# emonVS_mini.net
KiCad netlist of a schematic drawn in EAGLE
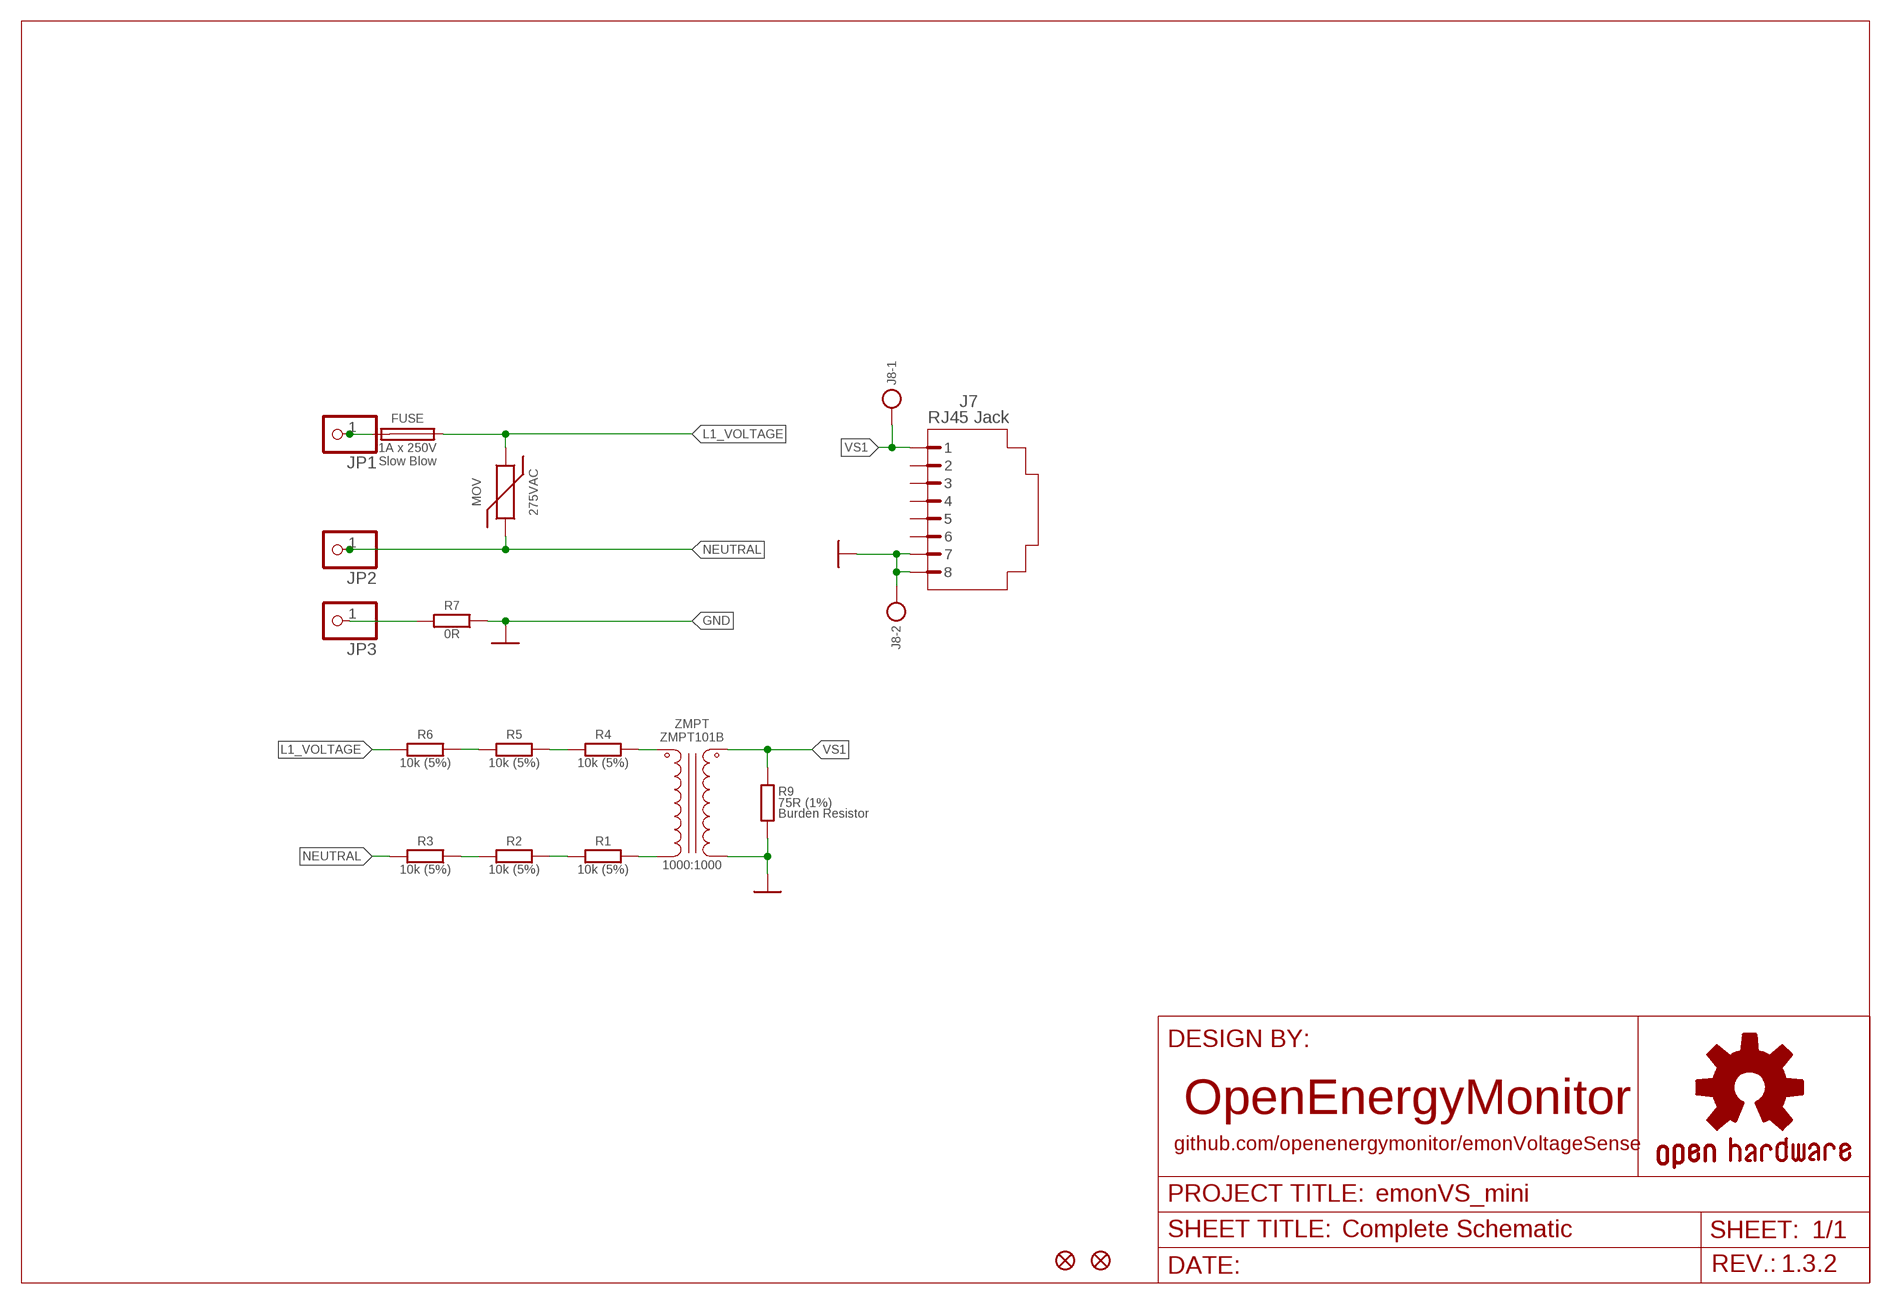
[diagram p0: schematic, sheet 1]

(export (version "E")
  (design (tool "Eeschema 10.0.6"))
  (components
    (comp (ref "FD1")
      (value "FIDUCIAL1X2")
      (footprint "eagle-import:FIDUCIAL")
      (libsource (lib "eagle-import") (part "FIDUCIAL1X2"))
    )
    (comp (ref "FD2")
      (value "FIDUCIAL1X2")
      (footprint "eagle-import:FIDUCIAL")
      (libsource (lib "eagle-import") (part "FIDUCIAL1X2"))
    )
    (comp (ref "FUSE")
      (value "1A x 250V")
      (footprint "eagle-import:FUSE")
      (fields (field (name "FAMILY") "Slow Blow"))
      (libsource (lib "eagle-import") (part "FUSE"))
    )
    (comp (ref "J7")
      (value "RJ45 Jack")
      (footprint "eagle-import:RJ45-8P")
      (libsource (lib "eagle-import") (part "RJ45-8PPTH"))
    )
    (comp (ref "J8")
      (value "TERMINAL_BLOCK_2P")
      (footprint "eagle-import:TERMINAL_BLOCK_2P")
      (libsource (lib "eagle-import") (part "TERMINAL_BLOCK_2P"))
    )
    (comp (ref "JP1")
      (value "PINHD-1X1")
      (footprint "eagle-import:1X01")
      (libsource (lib "eagle-import") (part "PINHD-1X1"))
    )
    (comp (ref "JP2")
      (value "PINHD-1X1")
      (footprint "eagle-import:1X01")
      (libsource (lib "eagle-import") (part "PINHD-1X1"))
    )
    (comp (ref "JP3")
      (value "PINHD-1X1")
      (footprint "eagle-import:1X01")
      (libsource (lib "eagle-import") (part "PINHD-1X1"))
    )
    (comp (ref "MOV")
      (value "275VAC")
      (footprint "eagle-import:MOV")
      (libsource (lib "eagle-import") (part "MOV_14MM_275VAC"))
    )
    (comp (ref "R1")
      (value "10k (5%)")
      (footprint "eagle-import:R1206")
      (libsource (lib "eagle-import") (part "R_1206"))
    )
    (comp (ref "R2")
      (value "10k (5%)")
      (footprint "eagle-import:R1206")
      (libsource (lib "eagle-import") (part "R_1206"))
    )
    (comp (ref "R3")
      (value "10k (5%)")
      (footprint "eagle-import:R1206")
      (libsource (lib "eagle-import") (part "R_1206"))
    )
    (comp (ref "R4")
      (value "10k (5%)")
      (footprint "eagle-import:R1206")
      (libsource (lib "eagle-import") (part "R_1206"))
    )
    (comp (ref "R5")
      (value "10k (5%)")
      (footprint "eagle-import:R1206")
      (libsource (lib "eagle-import") (part "R_1206"))
    )
    (comp (ref "R6")
      (value "10k (5%)")
      (footprint "eagle-import:R1206")
      (libsource (lib "eagle-import") (part "R_1206"))
    )
    (comp (ref "R7")
      (value "0R")
      (footprint "eagle-import:R1206")
      (libsource (lib "eagle-import") (part "R_1206"))
    )
    (comp (ref "R9")
      (value "75R (1%)")
      (footprint "eagle-import:R_PTH_SMD")
      (description "Burden Resistor")
      (libsource (lib "eagle-import") (part "R_"))
    )
    (comp (ref "ZMPT")
      (value "ZMPT101B")
      (footprint "eagle-import:ZMPT101B")
      (fields (field (name "RATIO") "1000:1000"))
      (libsource (lib "eagle-import") (part "ZMPT101B"))
    )
  )
  (nets
    (net (code "1") (name "GND") (class "Default")
      (node (ref "J7") (pin "7") (pinfunction "7_7") (pintype "bidirectional"))
      (node (ref "J7") (pin "8") (pinfunction "8_8") (pintype "bidirectional"))
      (node (ref "J8") (pin "1") (pinfunction "P$1_1") (pintype "passive"))
      (node (ref "R7") (pin "1") (pinfunction "1_1") (pintype "passive"))
      (node (ref "R9") (pin "1A") (pinfunction "2_1A") (pintype "passive"))
      (node (ref "R9") (pin "1B") (pinfunction "2_1B") (pintype "passive"))
      (node (ref "ZMPT") (pin "4") (pinfunction "SEC_1_4") (pintype "bidirectional"))
    )
    (net (code "2") (name "L1_VOLTAGE") (class "Default")
      (node (ref "FUSE") (pin "OUT") (pinfunction "1_OUT") (pintype "passive"))
      (node (ref "MOV") (pin "1") (pinfunction "2_1") (pintype "bidirectional"))
      (node (ref "R6") (pin "2") (pinfunction "2_2") (pintype "passive"))
    )
    (net (code "3") (name "NEUTRAL") (class "Default")
      (node (ref "JP2") (pin "1") (pinfunction "1_1") (pintype "passive"))
      (node (ref "MOV") (pin "2") (pinfunction "1_2") (pintype "bidirectional"))
      (node (ref "R3") (pin "2") (pinfunction "2_2") (pintype "passive"))
    )
    (net (code "4") (name "Net-(FUSE-2)") (class "Default")
      (node (ref "FUSE") (pin "IN") (pinfunction "2_IN") (pintype "passive"))
      (node (ref "JP1") (pin "1") (pinfunction "1_1") (pintype "passive"))
    )
    (net (code "5") (name "Net-(JP3-Pad1)") (class "Default")
      (node (ref "JP3") (pin "1") (pinfunction "1_1") (pintype "passive"))
      (node (ref "R7") (pin "2") (pinfunction "2_2") (pintype "passive"))
    )
    (net (code "6") (name "Net-(R1-Pad2)") (class "Default")
      (node (ref "R1") (pin "2") (pinfunction "2_2") (pintype "passive"))
      (node (ref "R2") (pin "1") (pinfunction "1_1") (pintype "passive"))
    )
    (net (code "7") (name "Net-(R2-Pad2)") (class "Default")
      (node (ref "R2") (pin "2") (pinfunction "2_2") (pintype "passive"))
      (node (ref "R3") (pin "1") (pinfunction "1_1") (pintype "passive"))
    )
    (net (code "8") (name "Net-(R4-Pad2)") (class "Default")
      (node (ref "R4") (pin "2") (pinfunction "2_2") (pintype "passive"))
      (node (ref "R5") (pin "1") (pinfunction "1_1") (pintype "passive"))
    )
    (net (code "9") (name "Net-(R5-Pad2)") (class "Default")
      (node (ref "R5") (pin "2") (pinfunction "2_2") (pintype "passive"))
      (node (ref "R6") (pin "1") (pinfunction "1_1") (pintype "passive"))
    )
    (net (code "10") (name "Net-(ZMPT-PRI_1)") (class "Default")
      (node (ref "R4") (pin "1") (pinfunction "1_1") (pintype "passive"))
      (node (ref "ZMPT") (pin "2") (pinfunction "PRI_1_2") (pintype "bidirectional"))
    )
    (net (code "11") (name "Net-(ZMPT-PRI_2)") (class "Default")
      (node (ref "R1") (pin "1") (pinfunction "1_1") (pintype "passive"))
      (node (ref "ZMPT") (pin "1") (pinfunction "PRI_2_1") (pintype "bidirectional"))
    )
    (net (code "12") (name "VS1") (class "Default")
      (node (ref "J7") (pin "1") (pinfunction "1_1") (pintype "bidirectional"))
      (node (ref "J8") (pin "2") (pinfunction "P$1_2") (pintype "passive"))
      (node (ref "R9") (pin "2A") (pinfunction "1_2A") (pintype "passive"))
      (node (ref "R9") (pin "2B") (pinfunction "1_2B") (pintype "passive"))
      (node (ref "ZMPT") (pin "3") (pinfunction "SEC_2_3") (pintype "bidirectional"))
    )
    (net (code "13") (name "unconnected-(J7-Pad2)") (class "Default")
      (node (ref "J7") (pin "2") (pinfunction "2_2") (pintype "bidirectional"))
    )
    (net (code "14") (name "unconnected-(J7-Pad3)") (class "Default")
      (node (ref "J7") (pin "3") (pinfunction "3_3") (pintype "bidirectional"))
    )
    (net (code "15") (name "unconnected-(J7-Pad4)") (class "Default")
      (node (ref "J7") (pin "4") (pinfunction "4_4") (pintype "bidirectional"))
    )
    (net (code "16") (name "unconnected-(J7-Pad5)") (class "Default")
      (node (ref "J7") (pin "5") (pinfunction "5_5") (pintype "bidirectional"))
    )
    (net (code "17") (name "unconnected-(J7-Pad6)") (class "Default")
      (node (ref "J7") (pin "6") (pinfunction "6_6") (pintype "bidirectional"))
    )
  )
)
